# DCC_sDecoder.net
KiCad netlist of a schematic drawn in EAGLE
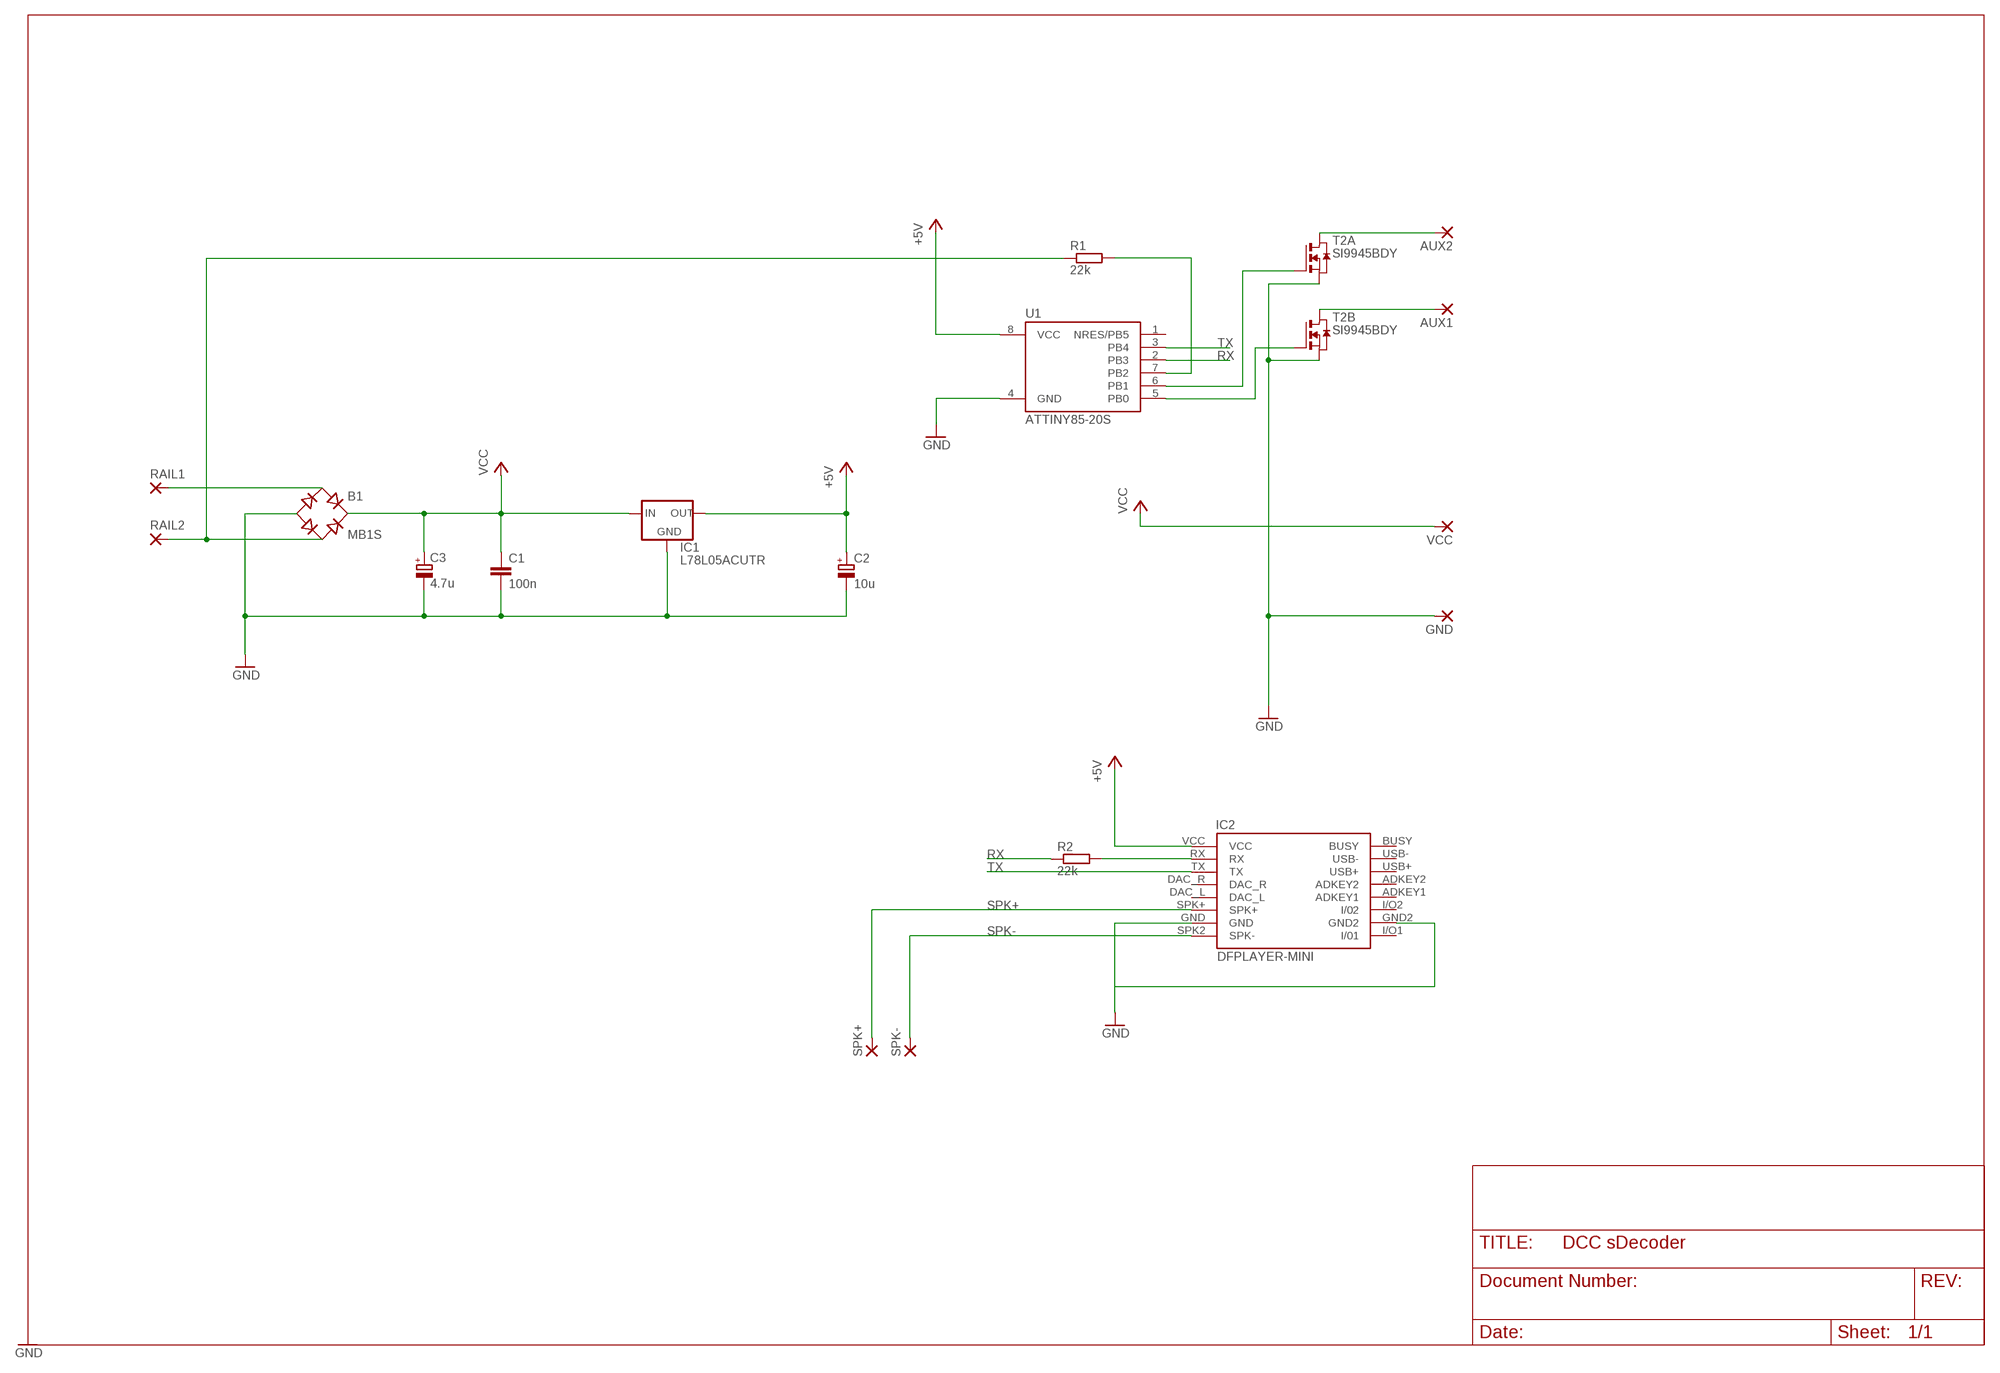
[diagram p0: schematic, sheet 1]

(export (version "E")
  (design (tool "Eeschema 10.0.6"))
  (components
    (comp (ref "AUX1")
      (value "SMD2")
      (footprint "eagle-import:SMD1,27-2,54")
      (libsource (lib "eagle-import") (part "SMD2"))
    )
    (comp (ref "AUX2")
      (value "SMD2")
      (footprint "eagle-import:SMD1,27-2,54")
      (libsource (lib "eagle-import") (part "SMD2"))
    )
    (comp (ref "B1")
      (value "MB1S")
      (footprint "eagle-import:SOIC-4")
      (libsource (lib "eagle-import") (part "MBS1"))
    )
    (comp (ref "C1")
      (value "100n")
      (footprint "eagle-import:C0805")
      (libsource (lib "eagle-import") (part "C-EUC0805"))
    )
    (comp (ref "C2")
      (value "10u")
      (footprint "eagle-import:A_3216-18W")
      (libsource (lib "eagle-import") (part "CPOL-EUA/3216-18W"))
    )
    (comp (ref "C3")
      (value "4.7u")
      (footprint "eagle-import:A_3216-18W")
      (libsource (lib "eagle-import") (part "CPOL-EUA/3216-18W"))
    )
    (comp (ref "GND")
      (value "SMD2")
      (footprint "eagle-import:SMD1,27-2,54")
      (libsource (lib "eagle-import") (part "SMD2"))
    )
    (comp (ref "IC1")
      (value "L78L05ACUTR")
      (footprint "eagle-import:SOT89R")
      (libsource (lib "eagle-import") (part "L78L05ACUTR"))
    )
    (comp (ref "IC2")
      (value "DFPLAYER-MINI")
      (footprint "eagle-import:DFPLAYER-MINI")
      (libsource (lib "eagle-import") (part "DFPLAYER-MINI"))
    )
    (comp (ref "R1")
      (value "22k")
      (footprint "eagle-import:R0805")
      (libsource (lib "eagle-import") (part "R-EU_R0805"))
    )
    (comp (ref "R2")
      (value "22k")
      (footprint "eagle-import:R0805")
      (libsource (lib "eagle-import") (part "R-EU_R0805"))
    )
    (comp (ref "RAIL1")
      (value "SMD2")
      (footprint "eagle-import:SMD1,27-2,54")
      (libsource (lib "eagle-import") (part "SMD2"))
    )
    (comp (ref "RAIL2")
      (value "SMD2")
      (footprint "eagle-import:SMD1,27-2,54")
      (libsource (lib "eagle-import") (part "SMD2"))
    )
    (comp (ref "SPK+")
      (value "SMD2")
      (footprint "eagle-import:SMD1,27-2,54")
      (libsource (lib "eagle-import") (part "SMD2"))
    )
    (comp (ref "SPK-")
      (value "SMD2")
      (footprint "eagle-import:SMD1,27-2,54")
      (libsource (lib "eagle-import") (part "SMD2"))
    )
    (comp (ref "T2")
      (value "SI9945BDY")
      (footprint "eagle-import:SO8")
      (libsource (lib "eagle-import") (part "NMOS2SO8"))
    )
    (comp (ref "U1")
      (value "ATTINY85-20S")
      (footprint "eagle-import:SOIC8_EIAJ_208MIL")
      (libsource (lib "eagle-import") (part "ATTINY85S-20"))
    )
    (comp (ref "VCC")
      (value "SMD2")
      (footprint "eagle-import:SMD1,27-2,54")
      (libsource (lib "eagle-import") (part "SMD2"))
    )
  )
  (nets
    (net (code "1") (name "+5V") (class "Default")
      (node (ref "C2") (pin "+") (pinfunction "+_+") (pintype "passive"))
      (node (ref "IC1") (pin "2") (pinfunction "OUT_2") (pintype "passive"))
      (node (ref "IC2") (pin "VCC") (pinfunction "VCC_VCC") (pintype "bidirectional"))
      (node (ref "U1") (pin "8") (pinfunction "VCC_8") (pintype "power_in"))
    )
    (net (code "2") (name "/RX") (class "Default")
      (node (ref "R2") (pin "1") (pinfunction "1_1") (pintype "passive"))
      (node (ref "U1") (pin "2") (pinfunction "PB3_2") (pintype "bidirectional"))
    )
    (net (code "3") (name "/SPK+") (class "Default")
      (node (ref "IC2") (pin "SPK+") (pinfunction "SPK+_SPK+") (pintype "bidirectional"))
      (node (ref "SPK+") (pin "1") (pinfunction "P_1") (pintype "passive"))
    )
    (net (code "4") (name "/SPK-") (class "Default")
      (node (ref "IC2") (pin "SPK2") (pinfunction "SPK-_SPK2") (pintype "bidirectional"))
      (node (ref "SPK-") (pin "1") (pinfunction "P_1") (pintype "passive"))
    )
    (net (code "5") (name "/TX") (class "Default")
      (node (ref "IC2") (pin "TX") (pinfunction "TX_TX") (pintype "bidirectional"))
      (node (ref "U1") (pin "3") (pinfunction "PB4_3") (pintype "bidirectional"))
    )
    (net (code "6") (name "GND") (class "Default")
      (node (ref "B1") (pin "-") (pinfunction "-_-") (pintype "passive"))
      (node (ref "C1") (pin "2") (pinfunction "2_2") (pintype "passive"))
      (node (ref "C2") (pin "-") (pinfunction "-_-") (pintype "passive"))
      (node (ref "C3") (pin "-") (pinfunction "-_-") (pintype "passive"))
      (node (ref "GND") (pin "1") (pinfunction "P_1") (pintype "passive"))
      (node (ref "IC1") (pin "3") (pinfunction "GND_3") (pintype "input"))
      (node (ref "IC1") (pin "4") (pinfunction "GND_4") (pintype "input"))
      (node (ref "IC2") (pin "GND") (pinfunction "GND_GND") (pintype "bidirectional"))
      (node (ref "IC2") (pin "GND2") (pinfunction "GND2_GND2") (pintype "bidirectional"))
      (node (ref "T2") (pin "1") (pinfunction "S_1") (pintype "passive"))
      (node (ref "T2") (pin "3") (pinfunction "S_3") (pintype "passive"))
      (node (ref "U1") (pin "4") (pinfunction "GND_4") (pintype "power_in"))
    )
    (net (code "7") (name "Net-(AUX1-P)") (class "Default")
      (node (ref "AUX1") (pin "1") (pinfunction "P_1") (pintype "passive"))
      (node (ref "T2") (pin "5") (pinfunction "D_5") (pintype "passive"))
      (node (ref "T2") (pin "6") (pinfunction "D_6") (pintype "passive"))
    )
    (net (code "8") (name "Net-(AUX2-P)") (class "Default")
      (node (ref "AUX2") (pin "1") (pinfunction "P_1") (pintype "passive"))
      (node (ref "T2") (pin "7") (pinfunction "D_7") (pintype "passive"))
      (node (ref "T2") (pin "8") (pinfunction "D_8") (pintype "passive"))
    )
    (net (code "9") (name "Net-(B1-AC1)") (class "Default")
      (node (ref "B1") (pin "~1") (pinfunction "AC1_~1") (pintype "passive"))
      (node (ref "RAIL1") (pin "1") (pinfunction "P_1") (pintype "passive"))
    )
    (net (code "10") (name "Net-(B1-AC2)") (class "Default")
      (node (ref "B1") (pin "~2") (pinfunction "AC2_~2") (pintype "passive"))
      (node (ref "R1") (pin "1") (pinfunction "1_1") (pintype "passive"))
      (node (ref "RAIL2") (pin "1") (pinfunction "P_1") (pintype "passive"))
    )
    (net (code "11") (name "Net-(IC2-PadRX)") (class "Default")
      (node (ref "IC2") (pin "RX") (pinfunction "RX_RX") (pintype "bidirectional"))
      (node (ref "R2") (pin "2") (pinfunction "2_2") (pintype "passive"))
    )
    (net (code "12") (name "Net-(T2A-G)") (class "Default")
      (node (ref "T2") (pin "2") (pinfunction "G_2") (pintype "passive"))
      (node (ref "U1") (pin "6") (pinfunction "PB1_6") (pintype "bidirectional"))
    )
    (net (code "13") (name "Net-(T2B-G)") (class "Default")
      (node (ref "T2") (pin "4") (pinfunction "G_4") (pintype "passive"))
      (node (ref "U1") (pin "5") (pinfunction "PB0_5") (pintype "bidirectional"))
    )
    (net (code "14") (name "Net-(U1-PB2)") (class "Default")
      (node (ref "R1") (pin "2") (pinfunction "2_2") (pintype "passive"))
      (node (ref "U1") (pin "7") (pinfunction "PB2_7") (pintype "bidirectional"))
    )
    (net (code "15") (name "VCC") (class "Default")
      (node (ref "B1") (pin "+") (pinfunction "+_+") (pintype "passive"))
      (node (ref "C1") (pin "1") (pinfunction "1_1") (pintype "passive"))
      (node (ref "C3") (pin "+") (pinfunction "+_+") (pintype "passive"))
      (node (ref "IC1") (pin "1") (pinfunction "IN_1") (pintype "input"))
      (node (ref "VCC") (pin "1") (pinfunction "P_1") (pintype "passive"))
    )
    (net (code "16") (name "unconnected-(IC2-I{slash}01-PadI{slash}O1)") (class "Default")
      (node (ref "IC2") (pin "I/O1") (pinfunction "I/01_I/O1") (pintype "bidirectional"))
    )
    (net (code "17") (name "unconnected-(IC2-I{slash}02-PadI{slash}O2)") (class "Default")
      (node (ref "IC2") (pin "I/O2") (pinfunction "I/02_I/O2") (pintype "bidirectional"))
    )
    (net (code "18") (name "unconnected-(IC2-PadADKEY1)") (class "Default")
      (node (ref "IC2") (pin "ADKEY1") (pinfunction "ADKEY1_ADKEY1") (pintype "bidirectional"))
    )
    (net (code "19") (name "unconnected-(IC2-PadADKEY2)") (class "Default")
      (node (ref "IC2") (pin "ADKEY2") (pinfunction "ADKEY2_ADKEY2") (pintype "bidirectional"))
    )
    (net (code "20") (name "unconnected-(IC2-PadBUSY)") (class "Default")
      (node (ref "IC2") (pin "BUSY") (pinfunction "BUSY_BUSY") (pintype "bidirectional"))
    )
    (net (code "21") (name "unconnected-(IC2-PadDAC_L)") (class "Default")
      (node (ref "IC2") (pin "DAC_L") (pinfunction "DAC_L_DAC_L") (pintype "bidirectional"))
    )
    (net (code "22") (name "unconnected-(IC2-PadDAC_R)") (class "Default")
      (node (ref "IC2") (pin "DAC_R") (pinfunction "DAC_R_DAC_R") (pintype "bidirectional"))
    )
    (net (code "23") (name "unconnected-(IC2-PadUSB+)") (class "Default")
      (node (ref "IC2") (pin "USB+") (pinfunction "USB+_USB+") (pintype "bidirectional"))
    )
    (net (code "24") (name "unconnected-(IC2-PadUSB-)") (class "Default")
      (node (ref "IC2") (pin "USB-") (pinfunction "USB-_USB-") (pintype "bidirectional"))
    )
    (net (code "25") (name "unconnected-(U1-NRES{slash}PB5-Pad1)") (class "Default")
      (node (ref "U1") (pin "1") (pinfunction "NRES/PB5_1") (pintype "bidirectional"))
    )
  )
)
